# Buck.net
KiCad netlist of a schematic drawn in Altium Designer
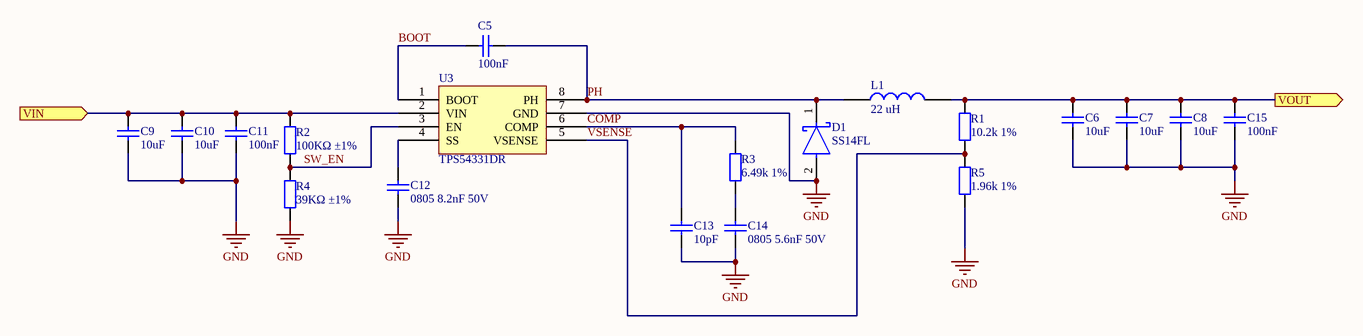
[diagram p0: Buck.SchDoc]

(export (version "E")
  (design (tool "Eeschema 10.0.6"))
  (components
    (comp (ref "C5")
      (value "100nF")
      (footprint "0603_C")
      (description "Chip capacitors")
      (fields (field (name "MANUFACTURER") "YAGEO") (field (name "PARTNUMBER") "CC0603KRX7R9BB104"))
      (libsource (lib "Miscellaneous Devices LC") (part "0603 100nF (104) 10% 50V"))
    )
    (comp (ref "C6")
      (value "10uF")
      (footprint "0603_C")
      (description "Chip capacitors")
      (fields
        (field (name "MANUFACTURER") "Samsung Electro-Mechanics")
        (field (name "PARTNUMBER") "CL10A106KP8NNNC")
      )
      (libsource (lib "Miscellaneous Devices LC") (part "0603 10uF (106) 10% 10V"))
    )
    (comp (ref "C7")
      (value "10uF")
      (footprint "0603_C")
      (description "Chip capacitors")
      (fields
        (field (name "MANUFACTURER") "Samsung Electro-Mechanics")
        (field (name "PARTNUMBER") "CL10A106KP8NNNC")
      )
      (libsource (lib "Miscellaneous Devices LC") (part "0603 10uF (106) 10% 10V"))
    )
    (comp (ref "C8")
      (value "10uF")
      (footprint "0603_C")
      (description "Chip capacitors")
      (fields
        (field (name "MANUFACTURER") "Samsung Electro-Mechanics")
        (field (name "PARTNUMBER") "CL10A106KP8NNNC")
      )
      (libsource (lib "Miscellaneous Devices LC") (part "0603 10uF (106) 10% 10V"))
    )
    (comp (ref "C9")
      (value "10uF")
      (footprint "0805_C")
      (description "Chip capacitors")
      (fields
        (field (name "MANUFACTURER") "Samsung Electro-Mechanics")
        (field (name "PARTNUMBER") "CL21A106KAYNNNE")
      )
      (libsource (lib "Miscellaneous Devices LC") (part "0805 10uF (106) 10% 25V"))
    )
    (comp (ref "C10")
      (value "10uF")
      (footprint "0805_C")
      (description "Chip capacitors")
      (fields
        (field (name "MANUFACTURER") "Samsung Electro-Mechanics")
        (field (name "PARTNUMBER") "CL21A106KAYNNNE")
      )
      (libsource (lib "Miscellaneous Devices LC") (part "0805 10uF (106) 10% 25V"))
    )
    (comp (ref "C11")
      (value "100nF")
      (footprint "0603_C")
      (description "Chip capacitors")
      (fields (field (name "MANUFACTURER") "YAGEO") (field (name "PARTNUMBER") "CC0603KRX7R9BB104"))
      (libsource (lib "Miscellaneous Devices LC") (part "0603 100nF (104) 10% 50V"))
    )
    (comp (ref "C12")
      (value "0805 8.2nF 50V")
      (footprint "Miscellaneous Devices LC:0805_C")
      (fields (field (name "PARTNUMBER") "CL21B822KBANNNC"))
      (libsource (lib "misc") (part "0805 8.2nF 50V"))
    )
    (comp (ref "C13")
      (value "10pF")
      (footprint "0603_C")
      (description "Chip capacitors")
      (fields
        (field (name "MANUFACTURER") "Samsung Electro-Mechanics")
        (field (name "PARTNUMBER") "CL10C100JB8NNNC")
      )
      (libsource (lib "Miscellaneous Devices LC") (part "0603 10pF (100) 5% 50V"))
    )
    (comp (ref "C14")
      (value "0805 5.6nF 50V")
      (footprint "Miscellaneous Devices LC:0805_C")
      (fields (field (name "PARTNUMBER") "CL21B562KBANNNC"))
      (libsource (lib "misc") (part "0805 5.6nF 50V"))
    )
    (comp (ref "C15")
      (value "100nF")
      (footprint "0603_C")
      (description "Chip capacitors")
      (fields (field (name "MANUFACTURER") "YAGEO") (field (name "PARTNUMBER") "CC0603KRX7R9BB104"))
      (libsource (lib "Miscellaneous Devices LC") (part "0603 100nF (104) 10% 50V"))
    )
    (comp (ref "D1")
      (value "SS14FL")
      (footprint "FP-425AD-MFG")
      (description "DIODE SCHOTTKY 40V 1A SOD123F")
      (fields
        (field (name "MANUFACTURER") "ON Semiconductor")
        (field (name "OCTOPART") "https://octopart.com/ss14fl-on+semiconductor-84331601")
      )
      (libsource (lib "Altium Content Vault") (part "c1678fac7984e62e0809fbf79c06691"))
    )
    (comp (ref "L1")
      (value "22 uH")
      (footprint "470")
      (libsource (lib "SWRB1204S-220MT") (part "SRP6540-5R6M"))
    )
    (comp (ref "R1")
      (value "10.2k 1%")
      (footprint "Miscellaneous Devices LC:1206_R")
      (fields (field (name "PARTNUMBER") "1206W4F1022T5E"))
      (libsource (lib "misc") (part "1206 10.2k 1%"))
    )
    (comp (ref "R2")
      (value "100KΩ ±1%")
      (footprint "0805_R")
      (description "Chip resistor")
      (fields (field (name "MANUFACTURER") "Uniroyal Elec") (field (name "POWER") "1/8W"))
      (libsource (lib "Miscellaneous Devices LC") (part "0805 100K (1003) 1%"))
    )
    (comp (ref "R3")
      (value "6.49k 1%")
      (footprint "Miscellaneous Devices LC:0805_R")
      (fields (field (name "PARTNUMBER") "0805W8F6491T5E"))
      (libsource (lib "misc") (part "0805 6.49k 1%"))
    )
    (comp (ref "R4")
      (value "39KΩ ±1%")
      (footprint "0805_R")
      (description "Chip resistor")
      (fields (field (name "MANUFACTURER") "Uniroyal Elec") (field (name "POWER") "1/8W"))
      (libsource (lib "Miscellaneous Devices LC") (part "0805 39K (3902) 1%"))
    )
    (comp (ref "R5")
      (value "1.96k 1%")
      (footprint "Miscellaneous Devices LC:1206_R")
      (fields (field (name "PARTNUMBER") "1206W4F1022T5E"))
      (libsource (lib "misc") (part "1206 1.96k 1%"))
    )
    (comp (ref "U3")
      (value "TPS54331DR")
      (footprint "SOIC-8_150mil")
      (description "DC-DC芯片")
      (libsource (lib "Miscellaneous Devices LC") (part "TPS54331DR_[C9865]"))
    )
  )
  (nets
    (net (code "1") (name "/BOOT") (class "Default")
      (node (ref "C5") (pin "2") (pinfunction "2_2") (pintype "passive"))
      (node (ref "U3") (pin "1") (pinfunction "BOOT_1") (pintype "passive"))
    )
    (net (code "2") (name "/COMP") (class "Default")
      (node (ref "C13") (pin "2") (pinfunction "2_2") (pintype "passive"))
      (node (ref "R3") (pin "2") (pinfunction "2_2") (pintype "passive"))
      (node (ref "U3") (pin "6") (pinfunction "COMP_6") (pintype "passive"))
    )
    (net (code "3") (name "/PH") (class "Default")
      (node (ref "C5") (pin "1") (pinfunction "1_1") (pintype "passive"))
      (node (ref "D1") (pin "1") (pinfunction "C_1") (pintype "passive"))
      (node (ref "L1") (pin "1") (pinfunction "1_1") (pintype "passive"))
      (node (ref "U3") (pin "8") (pinfunction "PH_8") (pintype "passive"))
    )
    (net (code "4") (name "/SW_EN") (class "Default")
      (node (ref "R2") (pin "2") (pinfunction "2_2") (pintype "passive"))
      (node (ref "R4") (pin "2") (pinfunction "2_2") (pintype "passive"))
      (node (ref "U3") (pin "3") (pinfunction "EN_3") (pintype "passive"))
    )
    (net (code "5") (name "/VIN") (class "Default")
      (node (ref "C10") (pin "2") (pinfunction "2_2") (pintype "passive"))
      (node (ref "C11") (pin "2") (pinfunction "2_2") (pintype "passive"))
      (node (ref "C9") (pin "2") (pinfunction "2_2") (pintype "passive"))
      (node (ref "R2") (pin "1") (pinfunction "1_1") (pintype "passive"))
      (node (ref "U3") (pin "2") (pinfunction "VIN_2") (pintype "passive"))
    )
    (net (code "6") (name "/VOUT") (class "Default")
      (node (ref "C15") (pin "2") (pinfunction "2_2") (pintype "passive"))
      (node (ref "C6") (pin "2") (pinfunction "2_2") (pintype "passive"))
      (node (ref "C7") (pin "2") (pinfunction "2_2") (pintype "passive"))
      (node (ref "C8") (pin "2") (pinfunction "2_2") (pintype "passive"))
      (node (ref "L1") (pin "2") (pinfunction "2_2") (pintype "passive"))
      (node (ref "R1") (pin "1") (pinfunction "1_1") (pintype "passive"))
    )
    (net (code "7") (name "/VSENSE") (class "Default")
      (node (ref "R1") (pin "2") (pinfunction "2_2") (pintype "passive"))
      (node (ref "R5") (pin "2") (pinfunction "2_2") (pintype "passive"))
      (node (ref "U3") (pin "5") (pinfunction "VSENSE_5") (pintype "passive"))
    )
    (net (code "8") (name "GND") (class "Default")
      (node (ref "C10") (pin "1") (pinfunction "1_1") (pintype "passive"))
      (node (ref "C11") (pin "1") (pinfunction "1_1") (pintype "passive"))
      (node (ref "C12") (pin "1") (pinfunction "1_1") (pintype "passive"))
      (node (ref "C13") (pin "1") (pinfunction "1_1") (pintype "passive"))
      (node (ref "C14") (pin "1") (pinfunction "1_1") (pintype "passive"))
      (node (ref "C15") (pin "1") (pinfunction "1_1") (pintype "passive"))
      (node (ref "C6") (pin "1") (pinfunction "1_1") (pintype "passive"))
      (node (ref "C7") (pin "1") (pinfunction "1_1") (pintype "passive"))
      (node (ref "C8") (pin "1") (pinfunction "1_1") (pintype "passive"))
      (node (ref "C9") (pin "1") (pinfunction "1_1") (pintype "passive"))
      (node (ref "D1") (pin "2") (pinfunction "A_2") (pintype "passive"))
      (node (ref "R4") (pin "1") (pinfunction "1_1") (pintype "passive"))
      (node (ref "R5") (pin "1") (pinfunction "1_1") (pintype "passive"))
      (node (ref "U3") (pin "7") (pinfunction "GND_7") (pintype "passive"))
    )
    (net (code "9") (name "Net-(C14-Pad2)") (class "Default")
      (node (ref "C14") (pin "2") (pinfunction "2_2") (pintype "passive"))
      (node (ref "R3") (pin "1") (pinfunction "1_1") (pintype "passive"))
    )
    (net (code "10") (name "Net-(U3-SS)") (class "Default")
      (node (ref "C12") (pin "2") (pinfunction "2_2") (pintype "passive"))
      (node (ref "U3") (pin "4") (pinfunction "SS_4") (pintype "passive"))
    )
  )
)
